# Battery_Front_End.net
KiCad netlist of a schematic drawn in Altium Designer
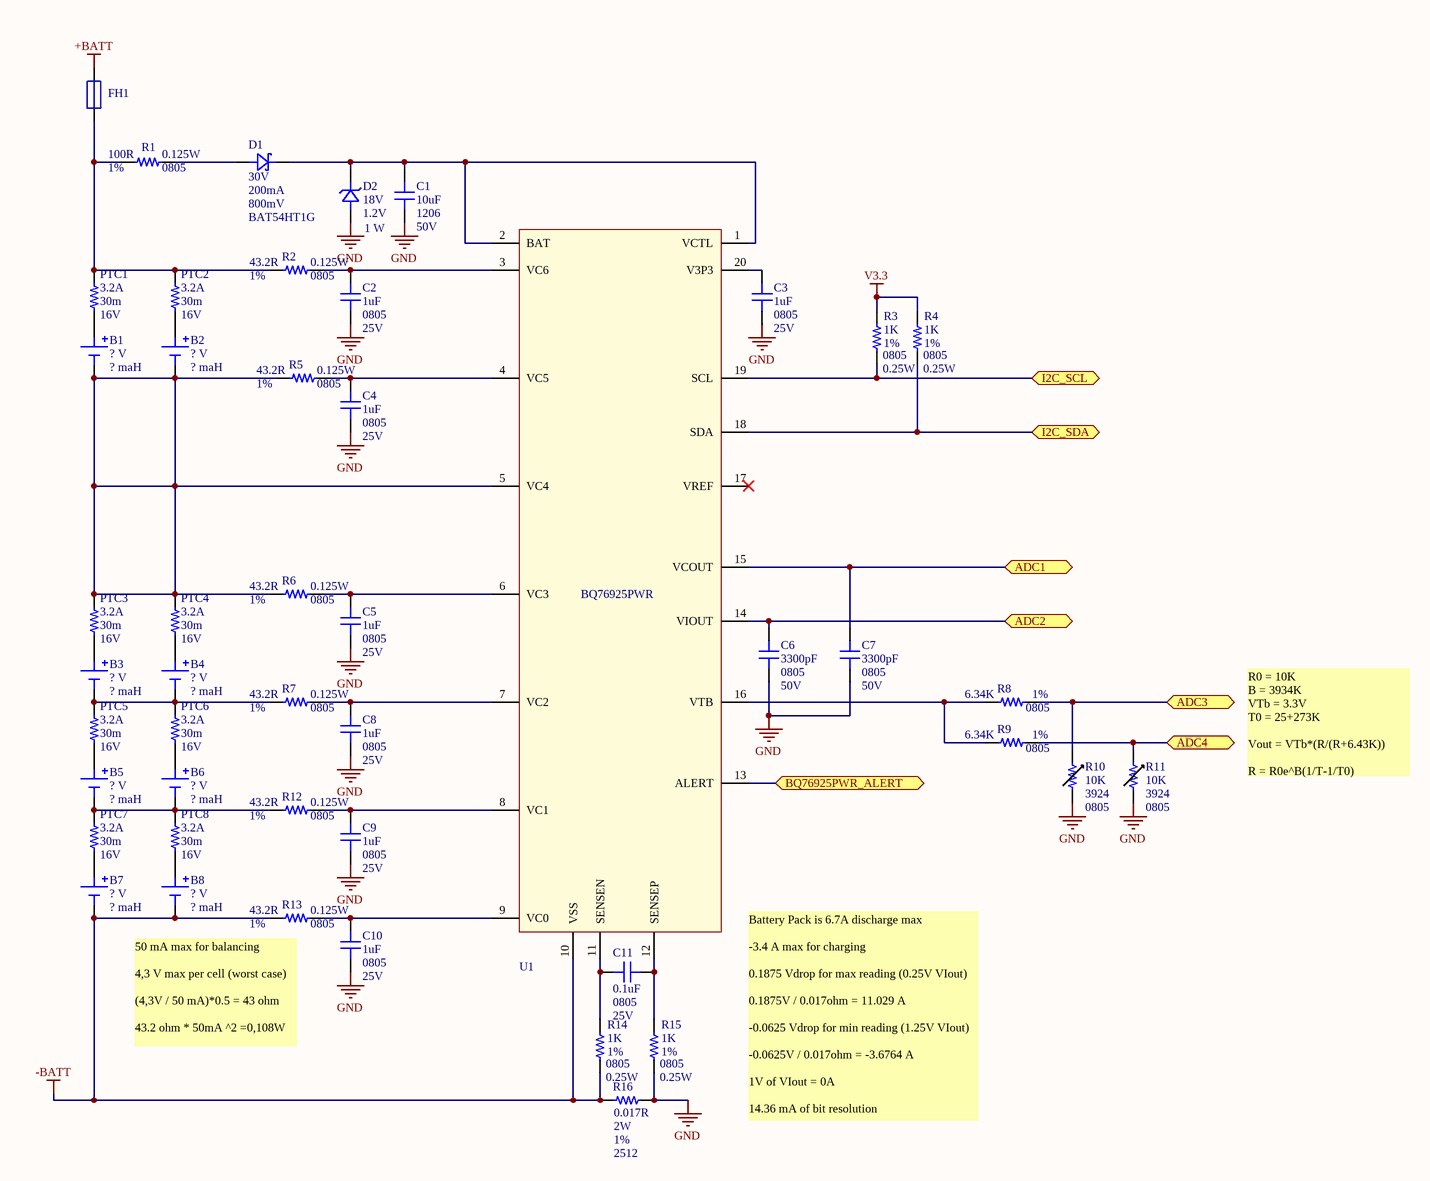
[diagram p0: Battery Front End.SchDoc]

(export (version "E")
  (design (tool "Eeschema 10.0.6"))
  (components
    (comp (ref "B1")
      (value "Battery Cell 18650")
      (footprint "18650 PC PIN")
      (fields (field (name "VOLTAGE") "? V") (field (name "CHARGE") "? maH"))
      (libsource (lib "SecureBot") (part "Battery Cell 18650"))
    )
    (comp (ref "B2")
      (value "Battery Cell 18650")
      (footprint "18650 PC PIN")
      (fields (field (name "VOLTAGE") "? V") (field (name "CHARGE") "? maH"))
      (libsource (lib "SecureBot") (part "Battery Cell 18650"))
    )
    (comp (ref "B3")
      (value "Battery Cell 18650")
      (footprint "18650 PC PIN")
      (fields (field (name "VOLTAGE") "? V") (field (name "CHARGE") "? maH"))
      (libsource (lib "SecureBot") (part "Battery Cell 18650"))
    )
    (comp (ref "B4")
      (value "Battery Cell 18650")
      (footprint "18650 PC PIN")
      (fields (field (name "VOLTAGE") "? V") (field (name "CHARGE") "? maH"))
      (libsource (lib "SecureBot") (part "Battery Cell 18650"))
    )
    (comp (ref "B5")
      (value "Battery Cell 18650")
      (footprint "18650 PC PIN")
      (fields (field (name "VOLTAGE") "? V") (field (name "CHARGE") "? maH"))
      (libsource (lib "SecureBot") (part "Battery Cell 18650"))
    )
    (comp (ref "B6")
      (value "Battery Cell 18650")
      (footprint "18650 PC PIN")
      (fields (field (name "VOLTAGE") "? V") (field (name "CHARGE") "? maH"))
      (libsource (lib "SecureBot") (part "Battery Cell 18650"))
    )
    (comp (ref "B7")
      (value "Battery Cell 18650")
      (footprint "18650 PC PIN")
      (fields (field (name "VOLTAGE") "? V") (field (name "CHARGE") "? maH"))
      (libsource (lib "SecureBot") (part "Battery Cell 18650"))
    )
    (comp (ref "B8")
      (value "Battery Cell 18650")
      (footprint "18650 PC PIN")
      (fields (field (name "VOLTAGE") "? V") (field (name "CHARGE") "? maH"))
      (libsource (lib "SecureBot") (part "Battery Cell 18650"))
    )
    (comp (ref "C1")
      (value "10uF")
      (footprint "CAP_1206")
      (description "CAP CER 10uF 50V 1206")
      (fields
        (field (name "PART NUMBER") "GRT31CR61H106ME01L‎")
        (field (name "PACKAGE") "1206")
        (field (name "VOLTAGE") "50V")
        (field (name "Comment") "CAP_GRT31CR61H106ME01L‎")
      )
      (libsource (lib "SecureBot") (part "CAP_GRT31CR61H106ME01L‎"))
    )
    (comp (ref "C2")
      (value "1uF")
      (footprint "CAP_0805")
      (description "CAP CER 1uF 25V 0805")
      (fields
        (field (name "PART NUMBER") "CL21B105KAFNNNE‎")
        (field (name "PACKAGE") "0805")
        (field (name "VOLTAGE") "25V")
        (field (name "Comment") "CAP_‎‎‎‎CL21B105KAFNNNE‎")
      )
      (libsource (lib "SecureBot") (part "CAP_‎‎‎‎CL21B105KAFNNNE‎"))
    )
    (comp (ref "C3")
      (value "1uF")
      (footprint "CAP_0805")
      (description "CAP CER 1uF 25V 0805")
      (fields
        (field (name "PART NUMBER") "CL21B105KAFNNNE‎")
        (field (name "PACKAGE") "0805")
        (field (name "VOLTAGE") "25V")
        (field (name "Comment") "CAP_‎‎‎‎CL21B105KAFNNNE‎")
      )
      (libsource (lib "SecureBot") (part "CAP_‎‎‎‎CL21B105KAFNNNE‎"))
    )
    (comp (ref "C4")
      (value "1uF")
      (footprint "CAP_0805")
      (description "CAP CER 1uF 25V 0805")
      (fields
        (field (name "PART NUMBER") "CL21B105KAFNNNE‎")
        (field (name "PACKAGE") "0805")
        (field (name "VOLTAGE") "25V")
        (field (name "Comment") "CAP_‎‎‎‎CL21B105KAFNNNE‎")
      )
      (libsource (lib "SecureBot") (part "CAP_‎‎‎‎CL21B105KAFNNNE‎"))
    )
    (comp (ref "C5")
      (value "1uF")
      (footprint "CAP_0805")
      (description "CAP CER 1uF 25V 0805")
      (fields
        (field (name "PART NUMBER") "CL21B105KAFNNNE‎")
        (field (name "PACKAGE") "0805")
        (field (name "VOLTAGE") "25V")
        (field (name "Comment") "CAP_‎‎‎‎CL21B105KAFNNNE‎")
      )
      (libsource (lib "SecureBot") (part "CAP_‎‎‎‎CL21B105KAFNNNE‎"))
    )
    (comp (ref "C6")
      (value "3300pF")
      (footprint "CAP_0805")
      (description "CAP CER 3300pF 50V 0805")
      (fields
        (field (name "PART NUMBER") "CL21B332KBANNNC‎")
        (field (name "PACKAGE") "0805")
        (field (name "VOLTAGE") "50V")
        (field (name "Comment") "CAP_CL21B332KBANNNC‎")
      )
      (libsource (lib "SecureBot") (part "CAP_CL21B332KBANNNC‎"))
    )
    (comp (ref "C7")
      (value "3300pF")
      (footprint "CAP_0805")
      (description "CAP CER 3300pF 50V 0805")
      (fields
        (field (name "PART NUMBER") "CL21B332KBANNNC‎")
        (field (name "PACKAGE") "0805")
        (field (name "VOLTAGE") "50V")
        (field (name "Comment") "CAP_CL21B332KBANNNC‎")
      )
      (libsource (lib "SecureBot") (part "CAP_CL21B332KBANNNC‎"))
    )
    (comp (ref "C8")
      (value "1uF")
      (footprint "CAP_0805")
      (description "CAP CER 1uF 25V 0805")
      (fields
        (field (name "PART NUMBER") "CL21B105KAFNNNE‎")
        (field (name "PACKAGE") "0805")
        (field (name "VOLTAGE") "25V")
        (field (name "Comment") "CAP_‎‎‎‎CL21B105KAFNNNE‎")
      )
      (libsource (lib "SecureBot") (part "CAP_‎‎‎‎CL21B105KAFNNNE‎"))
    )
    (comp (ref "C9")
      (value "1uF")
      (footprint "CAP_0805")
      (description "CAP CER 1uF 25V 0805")
      (fields
        (field (name "PART NUMBER") "CL21B105KAFNNNE‎")
        (field (name "PACKAGE") "0805")
        (field (name "VOLTAGE") "25V")
        (field (name "Comment") "CAP_‎‎‎‎CL21B105KAFNNNE‎")
      )
      (libsource (lib "SecureBot") (part "CAP_‎‎‎‎CL21B105KAFNNNE‎"))
    )
    (comp (ref "C10")
      (value "1uF")
      (footprint "CAP_0805")
      (description "CAP CER 1uF 25V 0805")
      (fields
        (field (name "PART NUMBER") "CL21B105KAFNNNE‎")
        (field (name "PACKAGE") "0805")
        (field (name "VOLTAGE") "25V")
        (field (name "Comment") "CAP_‎‎‎‎CL21B105KAFNNNE‎")
      )
      (libsource (lib "SecureBot") (part "CAP_‎‎‎‎CL21B105KAFNNNE‎"))
    )
    (comp (ref "C11")
      (value "0.1uF")
      (footprint "CAP_0805")
      (description "CAP CER 0.1uF 25V 0805")
      (fields
        (field (name "PART NUMBER") "CC0805KRX7R8BB104‎")
        (field (name "PACKAGE") "0805")
        (field (name "VOLTAGE") "25V")
        (field (name "Comment") "CAP_‎‎CC0805KRX7R8BB104‎")
      )
      (libsource (lib "SecureBot") (part "CAP_‎‎CC0805KRX7R8BB104‎"))
    )
    (comp (ref "D1")
      (value "DIODE_SCH_BAT54HT1G")
      (footprint "SOD-323")
      (description "Diode Schottky 30V 200mA (DC)")
      (fields
        (field (name "VOLTAGE") "30V")
        (field (name "CURRENT") "200mA")
        (field (name "VF") "800mV")
        (field (name "PART NUMBER") "BAT54HT1G")
      )
      (libsource (lib "SecureBot") (part "DIODE_SCH_BAT54HT1G"))
    )
    (comp (ref "D2")
      (value "DIODE_ZEN_SMAZ18-13-F")
      (footprint "DO-214AC")
      (description "Diode Zener 18V 1W ±5%")
      (fields
        (field (name "VOLTAGE") "18V")
        (field (name "VF") "1.2V")
        (field (name "PART NUMBER") "SMAZ18-13-F")
        (field (name "POWER") "1 W")
      )
      (libsource (lib "SecureBot") (part "DIODE_ZEN_SMAZ18-13-F"))
    )
    (comp (ref "FH1")
      (value "FH 3AB-3AG")
      (footprint "FH_3AB_3AG")
      (description "Fuse holder (3AB-3AG)")
      (libsource (lib "SecureBot") (part "FH 3AB-3AG"))
    )
    (comp (ref "PTC1")
      (value "PTC_0ZCG0160BF2C")
      (footprint "PTC - 1812")
      (description "PTC_Polymeric PTC Resettable Fuse 16V 1.6A Ih")
      (fields
        (field (name "PART NUMBER") "0ZCG0160BF2C")
        (field (name "TRIP VALUE") "3.2A")
        (field (name "RES") "30m")
        (field (name "VOLTAGE") "16V")
      )
      (libsource (lib "SecureBot") (part "PTC_0ZCG0160BF2C"))
    )
    (comp (ref "PTC2")
      (value "PTC_0ZCG0160BF2C")
      (footprint "PTC - 1812")
      (description "PTC_Polymeric PTC Resettable Fuse 16V 1.6A Ih")
      (fields
        (field (name "PART NUMBER") "0ZCG0160BF2C")
        (field (name "TRIP VALUE") "3.2A")
        (field (name "RES") "30m")
        (field (name "VOLTAGE") "16V")
      )
      (libsource (lib "SecureBot") (part "PTC_0ZCG0160BF2C"))
    )
    (comp (ref "PTC3")
      (value "PTC_0ZCG0160BF2C")
      (footprint "PTC - 1812")
      (description "PTC_Polymeric PTC Resettable Fuse 16V 1.6A Ih")
      (fields
        (field (name "PART NUMBER") "0ZCG0160BF2C")
        (field (name "TRIP VALUE") "3.2A")
        (field (name "RES") "30m")
        (field (name "VOLTAGE") "16V")
      )
      (libsource (lib "SecureBot") (part "PTC_0ZCG0160BF2C"))
    )
    (comp (ref "PTC4")
      (value "PTC_0ZCG0160BF2C")
      (footprint "PTC - 1812")
      (description "PTC_Polymeric PTC Resettable Fuse 16V 1.6A Ih")
      (fields
        (field (name "PART NUMBER") "0ZCG0160BF2C")
        (field (name "TRIP VALUE") "3.2A")
        (field (name "RES") "30m")
        (field (name "VOLTAGE") "16V")
      )
      (libsource (lib "SecureBot") (part "PTC_0ZCG0160BF2C"))
    )
    (comp (ref "PTC5")
      (value "PTC_0ZCG0160BF2C")
      (footprint "PTC - 1812")
      (description "PTC_Polymeric PTC Resettable Fuse 16V 1.6A Ih")
      (fields
        (field (name "PART NUMBER") "0ZCG0160BF2C")
        (field (name "TRIP VALUE") "3.2A")
        (field (name "RES") "30m")
        (field (name "VOLTAGE") "16V")
      )
      (libsource (lib "SecureBot") (part "PTC_0ZCG0160BF2C"))
    )
    (comp (ref "PTC6")
      (value "PTC_0ZCG0160BF2C")
      (footprint "PTC - 1812")
      (description "PTC_Polymeric PTC Resettable Fuse 16V 1.6A Ih")
      (fields
        (field (name "PART NUMBER") "0ZCG0160BF2C")
        (field (name "TRIP VALUE") "3.2A")
        (field (name "RES") "30m")
        (field (name "VOLTAGE") "16V")
      )
      (libsource (lib "SecureBot") (part "PTC_0ZCG0160BF2C"))
    )
    (comp (ref "PTC7")
      (value "PTC_0ZCG0160BF2C")
      (footprint "PTC - 1812")
      (description "PTC_Polymeric PTC Resettable Fuse 16V 1.6A Ih")
      (fields
        (field (name "PART NUMBER") "0ZCG0160BF2C")
        (field (name "TRIP VALUE") "3.2A")
        (field (name "RES") "30m")
        (field (name "VOLTAGE") "16V")
      )
      (libsource (lib "SecureBot") (part "PTC_0ZCG0160BF2C"))
    )
    (comp (ref "PTC8")
      (value "PTC_0ZCG0160BF2C")
      (footprint "PTC - 1812")
      (description "PTC_Polymeric PTC Resettable Fuse 16V 1.6A Ih")
      (fields
        (field (name "PART NUMBER") "0ZCG0160BF2C")
        (field (name "TRIP VALUE") "3.2A")
        (field (name "RES") "30m")
        (field (name "VOLTAGE") "16V")
      )
      (libsource (lib "SecureBot") (part "PTC_0ZCG0160BF2C"))
    )
    (comp (ref "R1")
      (value "100R")
      (footprint "RES_0805")
      (description "RES 100R 1% 1/8W 0805")
      (fields
        (field (name "PART NUMBER") "‎ERA-6AEB101V‎")
        (field (name "PACKAGE") "0805")
        (field (name "POWER") "0.125W")
        (field (name "TOLERANCE") "1%")
        (field (name "Comment") "RES_‎‎‎ERA-6AEB101V‎")
      )
      (libsource (lib "SecureBot") (part "RES_‎‎‎ERA-6AEB101V‎"))
    )
    (comp (ref "R2")
      (value "43.2R")
      (footprint "RES_0805")
      (description "RES 43.2R 1% 1/8W 0805")
      (fields
        (field (name "PART NUMBER") "‎ERJ-6ENF43R2V‎")
        (field (name "PACKAGE") "0805")
        (field (name "POWER") "0.125W")
        (field (name "TOLERANCE") "1%")
        (field (name "Comment") "RES_‎ERJ-6ENF43R2V‎")
      )
      (libsource (lib "SecureBot") (part "RES_‎ERJ-6ENF43R2V‎"))
    )
    (comp (ref "R3")
      (value "1K")
      (footprint "RES_0805")
      (description "RES 1K 1% 1/4W 0805")
      (fields
        (field (name "PART NUMBER") "RNCP0805FTD1K00‎")
        (field (name "PACKAGE") "0805")
        (field (name "POWER") "0.25W")
        (field (name "TOLERANCE") "1%")
        (field (name "Comment") "RES_‎‎‎‎RNCP0805FTD1K00‎")
      )
      (libsource (lib "SecureBot") (part "RES_‎‎‎‎RNCP0805FTD1K00‎"))
    )
    (comp (ref "R4")
      (value "1K")
      (footprint "RES_0805")
      (description "RES 1K 1% 1/4W 0805")
      (fields
        (field (name "PART NUMBER") "RNCP0805FTD1K00‎")
        (field (name "PACKAGE") "0805")
        (field (name "POWER") "0.25W")
        (field (name "TOLERANCE") "1%")
        (field (name "Comment") "RES_‎‎‎‎RNCP0805FTD1K00‎")
      )
      (libsource (lib "SecureBot") (part "RES_‎‎‎‎RNCP0805FTD1K00‎"))
    )
    (comp (ref "R5")
      (value "43.2R")
      (footprint "RES_0805")
      (description "RES 43.2R 1% 1/8W 0805")
      (fields
        (field (name "PART NUMBER") "‎ERJ-6ENF43R2V‎")
        (field (name "PACKAGE") "0805")
        (field (name "POWER") "0.125W")
        (field (name "TOLERANCE") "1%")
        (field (name "Comment") "RES_‎ERJ-6ENF43R2V‎")
      )
      (libsource (lib "SecureBot") (part "RES_‎ERJ-6ENF43R2V‎"))
    )
    (comp (ref "R6")
      (value "43.2R")
      (footprint "RES_0805")
      (description "RES 43.2R 1% 1/8W 0805")
      (fields
        (field (name "PART NUMBER") "‎ERJ-6ENF43R2V‎")
        (field (name "PACKAGE") "0805")
        (field (name "POWER") "0.125W")
        (field (name "TOLERANCE") "1%")
        (field (name "Comment") "RES_‎ERJ-6ENF43R2V‎")
      )
      (libsource (lib "SecureBot") (part "RES_‎ERJ-6ENF43R2V‎"))
    )
    (comp (ref "R7")
      (value "43.2R")
      (footprint "RES_0805")
      (description "RES 43.2R 1% 1/8W 0805")
      (fields
        (field (name "PART NUMBER") "‎ERJ-6ENF43R2V‎")
        (field (name "PACKAGE") "0805")
        (field (name "POWER") "0.125W")
        (field (name "TOLERANCE") "1%")
        (field (name "Comment") "RES_‎ERJ-6ENF43R2V‎")
      )
      (libsource (lib "SecureBot") (part "RES_‎ERJ-6ENF43R2V‎"))
    )
    (comp (ref "R8")
      (value "6.34K")
      (footprint "RES_0805")
      (description "RES 6.34K 1% 1/8W 0805")
      (fields
        (field (name "PART NUMBER") "CRCW08056K34FKEA")
        (field (name "PACKAGE") "0805")
        (field (name "POWER") "0.125W")
        (field (name "TOLERANCE") "1%")
      )
      (libsource (lib "SecureBot") (part "RES_‎‎‎CRCW08056K34FKEA"))
    )
    (comp (ref "R9")
      (value "6.34K")
      (footprint "RES_0805")
      (description "RES 6.34K 1% 1/8W 0805")
      (fields
        (field (name "PART NUMBER") "CRCW08056K34FKEA")
        (field (name "PACKAGE") "0805")
        (field (name "POWER") "0.125W")
        (field (name "TOLERANCE") "1%")
      )
      (libsource (lib "SecureBot") (part "RES_‎‎‎CRCW08056K34FKEA"))
    )
    (comp (ref "R10")
      (value "RES_TH_NCP21XV103J03RA")
      (footprint "RES_0805")
      (description "Thermistor 10K - 0805")
      (fields
        (field (name "PART NUMBER") "SHYLPCKB")
        (field (name "RESISTANCE @ 25C") "10K")
        (field (name "B") "3924")
        (field (name "PACKAGE") "0805")
      )
      (libsource (lib "SecureBot") (part "RES_TH_NCP21XV103J03RA"))
    )
    (comp (ref "R11")
      (value "RES_TH_NCP21XV103J03RA")
      (footprint "RES_0805")
      (description "Thermistor 10K - 0805")
      (fields
        (field (name "PART NUMBER") "SHYLPCKB")
        (field (name "RESISTANCE @ 25C") "10K")
        (field (name "B") "3924")
        (field (name "PACKAGE") "0805")
      )
      (libsource (lib "SecureBot") (part "RES_TH_NCP21XV103J03RA"))
    )
    (comp (ref "R12")
      (value "43.2R")
      (footprint "RES_0805")
      (description "RES 43.2R 1% 1/8W 0805")
      (fields
        (field (name "PART NUMBER") "‎ERJ-6ENF43R2V‎")
        (field (name "PACKAGE") "0805")
        (field (name "POWER") "0.125W")
        (field (name "TOLERANCE") "1%")
        (field (name "Comment") "RES_‎ERJ-6ENF43R2V‎")
      )
      (libsource (lib "SecureBot") (part "RES_‎ERJ-6ENF43R2V‎"))
    )
    (comp (ref "R13")
      (value "43.2R")
      (footprint "RES_0805")
      (description "RES 43.2R 1% 1/8W 0805")
      (fields
        (field (name "PART NUMBER") "‎ERJ-6ENF43R2V‎")
        (field (name "PACKAGE") "0805")
        (field (name "POWER") "0.125W")
        (field (name "TOLERANCE") "1%")
        (field (name "Comment") "RES_‎ERJ-6ENF43R2V‎")
      )
      (libsource (lib "SecureBot") (part "RES_‎ERJ-6ENF43R2V‎"))
    )
    (comp (ref "R14")
      (value "1K")
      (footprint "RES_0805")
      (description "RES 1K 1% 1/4W 0805")
      (fields
        (field (name "PART NUMBER") "RNCP0805FTD1K00‎")
        (field (name "PACKAGE") "0805")
        (field (name "POWER") "0.25W")
        (field (name "TOLERANCE") "1%")
        (field (name "Comment") "RES_‎‎‎‎RNCP0805FTD1K00‎")
      )
      (libsource (lib "SecureBot") (part "RES_‎‎‎‎RNCP0805FTD1K00‎"))
    )
    (comp (ref "R15")
      (value "1K")
      (footprint "RES_0805")
      (description "RES 1K 1% 1/4W 0805")
      (fields
        (field (name "PART NUMBER") "RNCP0805FTD1K00‎")
        (field (name "PACKAGE") "0805")
        (field (name "POWER") "0.25W")
        (field (name "TOLERANCE") "1%")
        (field (name "Comment") "RES_‎‎‎‎RNCP0805FTD1K00‎")
      )
      (libsource (lib "SecureBot") (part "RES_‎‎‎‎RNCP0805FTD1K00‎"))
    )
    (comp (ref "R16")
      (value "0.017R")
      (footprint "RES_2512")
      (description "RES 0.017R 1% 2W 2512")
      (fields
        (field (name "PART NUMBER") "‎WSL2512R0170FEA18")
        (field (name "PACKAGE") "2512")
        (field (name "POWER") "2W")
        (field (name "TOLERANCE") "1%")
        (field (name "Comment") "RES_‎WSL2512R0170FEA18")
      )
      (libsource (lib "SecureBot") (part "RES_‎WSL2512R0170FEA18"))
    )
    (comp (ref "U1")
      (value "IC_BATT_BQ76925PWR")
      (footprint "BQ76925")
      (description "Battery management system")
      (fields (field (name "PART NUMBER") "BQ76925PWR"))
      (libsource (lib "SecureBot") (part "IC_BATT_BQ76925PWR"))
    )
  )
  (nets
    (net (code "1") (name "+BATT") (class "Default")
      (node (ref "FH1") (pin "2") (pinfunction "2_2") (pintype "passive"))
    )
    (net (code "2") (name "-BATT") (class "Default")
      (node (ref "B7") (pin "2") (pinfunction "2_2") (pintype "passive"))
      (node (ref "B8") (pin "2") (pinfunction "2_2") (pintype "passive"))
      (node (ref "R13") (pin "1") (pinfunction "1_1") (pintype "passive"))
      (node (ref "R14") (pin "2") (pinfunction "2_2") (pintype "passive"))
      (node (ref "R16") (pin "1") (pinfunction "1_1") (pintype "passive"))
      (node (ref "U1") (pin "10") (pinfunction "VSS_10") (pintype "passive"))
    )
    (net (code "3") (name "/ADC1") (class "Default")
      (node (ref "C7") (pin "1") (pinfunction "1_1") (pintype "passive"))
      (node (ref "U1") (pin "15") (pinfunction "VCOUT_15") (pintype "passive"))
    )
    (net (code "4") (name "/ADC2") (class "Default")
      (node (ref "C6") (pin "1") (pinfunction "1_1") (pintype "passive"))
      (node (ref "U1") (pin "14") (pinfunction "VIOUT_14") (pintype "passive"))
    )
    (net (code "5") (name "/ADC3") (class "Default")
      (node (ref "R10") (pin "1") (pinfunction "1_1") (pintype "passive"))
      (node (ref "R8") (pin "2") (pinfunction "2_2") (pintype "passive"))
    )
    (net (code "6") (name "/ADC4") (class "Default")
      (node (ref "R11") (pin "1") (pinfunction "1_1") (pintype "passive"))
      (node (ref "R9") (pin "2") (pinfunction "2_2") (pintype "passive"))
    )
    (net (code "7") (name "/BQ76925PWR_ALERT") (class "Default")
      (node (ref "U1") (pin "13") (pinfunction "ALERT_13") (pintype "passive"))
    )
    (net (code "8") (name "/I2C_SCL") (class "Default")
      (node (ref "R3") (pin "2") (pinfunction "2_2") (pintype "passive"))
      (node (ref "U1") (pin "19") (pinfunction "SCL_19") (pintype "passive"))
    )
    (net (code "9") (name "/I2C_SDA") (class "Default")
      (node (ref "R4") (pin "2") (pinfunction "2_2") (pintype "passive"))
      (node (ref "U1") (pin "18") (pinfunction "SDA_18") (pintype "passive"))
    )
    (net (code "10") (name "GND") (class "Default")
      (node (ref "C1") (pin "2") (pinfunction "2_2") (pintype "passive"))
      (node (ref "C10") (pin "2") (pinfunction "2_2") (pintype "passive"))
      (node (ref "C2") (pin "2") (pinfunction "2_2") (pintype "passive"))
      (node (ref "C3") (pin "2") (pinfunction "2_2") (pintype "passive"))
      (node (ref "C4") (pin "2") (pinfunction "2_2") (pintype "passive"))
      (node (ref "C5") (pin "2") (pinfunction "2_2") (pintype "passive"))
      (node (ref "C6") (pin "2") (pinfunction "2_2") (pintype "passive"))
      (node (ref "C7") (pin "2") (pinfunction "2_2") (pintype "passive"))
      (node (ref "C8") (pin "2") (pinfunction "2_2") (pintype "passive"))
      (node (ref "C9") (pin "2") (pinfunction "2_2") (pintype "passive"))
      (node (ref "D2") (pin "1") (pinfunction "1_1") (pintype "passive"))
      (node (ref "R10") (pin "2") (pinfunction "2_2") (pintype "passive"))
      (node (ref "R11") (pin "2") (pinfunction "2_2") (pintype "passive"))
      (node (ref "R15") (pin "2") (pinfunction "2_2") (pintype "passive"))
      (node (ref "R16") (pin "2") (pinfunction "2_2") (pintype "passive"))
    )
    (net (code "11") (name "Net-(B1-Pad1)") (class "Default")
      (node (ref "B1") (pin "1") (pinfunction "1_1") (pintype "passive"))
      (node (ref "PTC1") (pin "2") (pinfunction "2_2") (pintype "passive"))
    )
    (net (code "12") (name "Net-(B2-Pad1)") (class "Default")
      (node (ref "B2") (pin "1") (pinfunction "1_1") (pintype "passive"))
      (node (ref "PTC2") (pin "2") (pinfunction "2_2") (pintype "passive"))
    )
    (net (code "13") (name "Net-(B3-Pad1)") (class "Default")
      (node (ref "B3") (pin "1") (pinfunction "1_1") (pintype "passive"))
      (node (ref "PTC3") (pin "2") (pinfunction "2_2") (pintype "passive"))
    )
    (net (code "14") (name "Net-(B3-Pad2)") (class "Default")
      (node (ref "B3") (pin "2") (pinfunction "2_2") (pintype "passive"))
      (node (ref "B4") (pin "2") (pinfunction "2_2") (pintype "passive"))
      (node (ref "PTC5") (pin "1") (pinfunction "1_1") (pintype "passive"))
      (node (ref "PTC6") (pin "1") (pinfunction "1_1") (pintype "passive"))
      (node (ref "R7") (pin "1") (pinfunction "1_1") (pintype "passive"))
    )
    (net (code "15") (name "Net-(B4-Pad1)") (class "Default")
      (node (ref "B4") (pin "1") (pinfunction "1_1") (pintype "passive"))
      (node (ref "PTC4") (pin "2") (pinfunction "2_2") (pintype "passive"))
    )
    (net (code "16") (name "Net-(B5-Pad1)") (class "Default")
      (node (ref "B5") (pin "1") (pinfunction "1_1") (pintype "passive"))
      (node (ref "PTC5") (pin "2") (pinfunction "2_2") (pintype "passive"))
    )
    (net (code "17") (name "Net-(B5-Pad2)") (class "Default")
      (node (ref "B5") (pin "2") (pinfunction "2_2") (pintype "passive"))
      (node (ref "B6") (pin "2") (pinfunction "2_2") (pintype "passive"))
      (node (ref "PTC7") (pin "1") (pinfunction "1_1") (pintype "passive"))
      (node (ref "PTC8") (pin "1") (pinfunction "1_1") (pintype "passive"))
      (node (ref "R12") (pin "1") (pinfunction "1_1") (pintype "passive"))
    )
    (net (code "18") (name "Net-(B6-Pad1)") (class "Default")
      (node (ref "B6") (pin "1") (pinfunction "1_1") (pintype "passive"))
      (node (ref "PTC6") (pin "2") (pinfunction "2_2") (pintype "passive"))
    )
    (net (code "19") (name "Net-(B7-Pad1)") (class "Default")
      (node (ref "B7") (pin "1") (pinfunction "1_1") (pintype "passive"))
      (node (ref "PTC7") (pin "2") (pinfunction "2_2") (pintype "passive"))
    )
    (net (code "20") (name "Net-(B8-Pad1)") (class "Default")
      (node (ref "B8") (pin "1") (pinfunction "1_1") (pintype "passive"))
      (node (ref "PTC8") (pin "2") (pinfunction "2_2") (pintype "passive"))
    )
    (net (code "21") (name "Net-(D1-Pad1)") (class "Default")
      (node (ref "D1") (pin "1") (pinfunction "1_1") (pintype "passive"))
      (node (ref "R1") (pin "2") (pinfunction "2_2") (pintype "passive"))
    )
    (net (code "22") (name "Net-(FH1-Pad1)") (class "Default")
      (node (ref "FH1") (pin "1") (pinfunction "1_1") (pintype "passive"))
      (node (ref "PTC1") (pin "1") (pinfunction "1_1") (pintype "passive"))
      (node (ref "PTC2") (pin "1") (pinfunction "1_1") (pintype "passive"))
      (node (ref "R1") (pin "1") (pinfunction "1_1") (pintype "passive"))
      (node (ref "R2") (pin "1") (pinfunction "1_1") (pintype "passive"))
    )
    (net (code "23") (name "Net-(U1-BAT)") (class "Default")
      (node (ref "C1") (pin "1") (pinfunction "1_1") (pintype "passive"))
      (node (ref "D1") (pin "2") (pinfunction "2_2") (pintype "passive"))
      (node (ref "D2") (pin "2") (pinfunction "2_2") (pintype "passive"))
      (node (ref "U1") (pin "1") (pinfunction "VCTL_1") (pintype "passive"))
      (node (ref "U1") (pin "2") (pinfunction "BAT_2") (pintype "passive"))
    )
    (net (code "24") (name "Net-(U1-SENSEN)") (class "Default")
      (node (ref "C11") (pin "1") (pinfunction "1_1") (pintype "passive"))
      (node (ref "R14") (pin "1") (pinfunction "1_1") (pintype "passive"))
      (node (ref "U1") (pin "11") (pinfunction "SENSEN_11") (pintype "passive"))
    )
    (net (code "25") (name "Net-(U1-SENSEP)") (class "Default")
      (node (ref "C11") (pin "2") (pinfunction "2_2") (pintype "passive"))
      (node (ref "R15") (pin "1") (pinfunction "1_1") (pintype "passive"))
      (node (ref "U1") (pin "12") (pinfunction "SENSEP_12") (pintype "passive"))
    )
    (net (code "26") (name "Net-(U1-V3P3)") (class "Default")
      (node (ref "C3") (pin "1") (pinfunction "1_1") (pintype "passive"))
      (node (ref "U1") (pin "20") (pinfunction "V3P3_20") (pintype "passive"))
    )
    (net (code "27") (name "Net-(U1-VC0)") (class "Default")
      (node (ref "C10") (pin "1") (pinfunction "1_1") (pintype "passive"))
      (node (ref "R13") (pin "2") (pinfunction "2_2") (pintype "passive"))
      (node (ref "U1") (pin "9") (pinfunction "VC0_9") (pintype "passive"))
    )
    (net (code "28") (name "Net-(U1-VC1)") (class "Default")
      (node (ref "C9") (pin "1") (pinfunction "1_1") (pintype "passive"))
      (node (ref "R12") (pin "2") (pinfunction "2_2") (pintype "passive"))
      (node (ref "U1") (pin "8") (pinfunction "VC1_8") (pintype "passive"))
    )
    (net (code "29") (name "Net-(U1-VC2)") (class "Default")
      (node (ref "C8") (pin "1") (pinfunction "1_1") (pintype "passive"))
      (node (ref "R7") (pin "2") (pinfunction "2_2") (pintype "passive"))
      (node (ref "U1") (pin "7") (pinfunction "VC2_7") (pintype "passive"))
    )
    (net (code "30") (name "Net-(U1-VC3)") (class "Default")
      (node (ref "C5") (pin "1") (pinfunction "1_1") (pintype "passive"))
      (node (ref "R6") (pin "2") (pinfunction "2_2") (pintype "passive"))
      (node (ref "U1") (pin "6") (pinfunction "VC3_6") (pintype "passive"))
    )
    (net (code "31") (name "Net-(U1-VC4)") (class "Default")
      (node (ref "B1") (pin "2") (pinfunction "2_2") (pintype "passive"))
      (node (ref "B2") (pin "2") (pinfunction "2_2") (pintype "passive"))
      (node (ref "PTC3") (pin "1") (pinfunction "1_1") (pintype "passive"))
      (node (ref "PTC4") (pin "1") (pinfunction "1_1") (pintype "passive"))
      (node (ref "R5") (pin "1") (pinfunction "1_1") (pintype "passive"))
      (node (ref "R6") (pin "1") (pinfunction "1_1") (pintype "passive"))
      (node (ref "U1") (pin "5") (pinfunction "VC4_5") (pintype "passive"))
    )
    (net (code "32") (name "Net-(U1-VC5)") (class "Default")
      (node (ref "C4") (pin "1") (pinfunction "1_1") (pintype "passive"))
      (node (ref "R5") (pin "2") (pinfunction "2_2") (pintype "passive"))
      (node (ref "U1") (pin "4") (pinfunction "VC5_4") (pintype "passive"))
    )
    (net (code "33") (name "Net-(U1-VC6)") (class "Default")
      (node (ref "C2") (pin "1") (pinfunction "1_1") (pintype "passive"))
      (node (ref "R2") (pin "2") (pinfunction "2_2") (pintype "passive"))
      (node (ref "U1") (pin "3") (pinfunction "VC6_3") (pintype "passive"))
    )
    (net (code "34") (name "Net-(U1-VTB)") (class "Default")
      (node (ref "R8") (pin "1") (pinfunction "1_1") (pintype "passive"))
      (node (ref "R9") (pin "1") (pinfunction "1_1") (pintype "passive"))
      (node (ref "U1") (pin "16") (pinfunction "VTB_16") (pintype "passive"))
    )
    (net (code "35") (name "V3.3") (class "Default")
      (node (ref "R3") (pin "1") (pinfunction "1_1") (pintype "passive"))
      (node (ref "R4") (pin "1") (pinfunction "1_1") (pintype "passive"))
    )
    (net (code "36") (name "unconnected-(U1-VREF-Pad17)") (class "Default")
      (node (ref "U1") (pin "17") (pinfunction "VREF_17") (pintype "passive+no_connect"))
    )
  )
)
